# 11_CONSOLE.net
KiCad netlist of a schematic drawn in Altium Designer
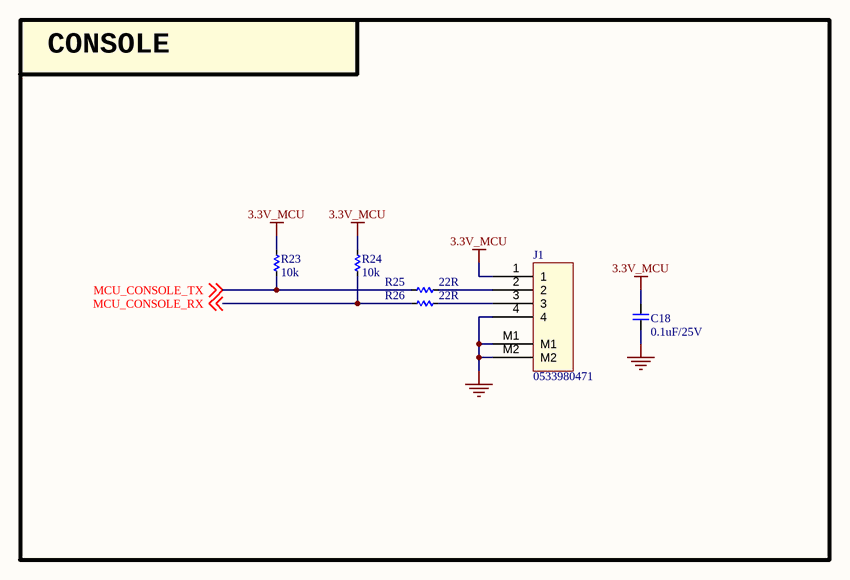
[diagram p0: 11_CONSOLE.SchDoc]

(export (version "E")
  (design (tool "Eeschema 10.0.6"))
  (components
    (comp (ref "C18")
      (value "0.1uF/25V")
      (footprint "CAP_C_1005X60")
      (description "CAP")
      (libsource (lib "LABLIB") (part "_CAP_C_2"))
    )
    (comp (ref "J1")
      (value "0533980471")
      (footprint "MOLEX_0533980471")
      (libsource (lib "LABLIB") (part "Header 4x1_2M"))
    )
    (comp (ref "R23")
      (value "10k")
      (footprint "RES_C_1005X40")
      (description "RES")
      (libsource (lib "LABLIB") (part "_RES_B_2"))
    )
    (comp (ref "R24")
      (value "10k")
      (footprint "RES_C_1005X40")
      (description "RES")
      (libsource (lib "LABLIB") (part "_RES_B_2"))
    )
    (comp (ref "R25")
      (value "22R")
      (footprint "RES_C_1005X40")
      (description "RES")
      (libsource (lib "LABLIB") (part "_RES_B_2"))
    )
    (comp (ref "R26")
      (value "22R")
      (footprint "RES_C_1005X40")
      (description "RES")
      (libsource (lib "LABLIB") (part "_RES_B_2"))
    )
  )
  (nets
    (net (code "1") (name "3.3V_MCU") (class "Default")
      (node (ref "C18") (pin "2") (pinfunction "2_2") (pintype "passive"))
      (node (ref "J1") (pin "1") (pinfunction "1_1") (pintype "passive"))
      (node (ref "R23") (pin "2") (pinfunction "2_2") (pintype "passive"))
      (node (ref "R24") (pin "2") (pinfunction "2_2") (pintype "passive"))
    )
    (net (code "2") (name "GND") (class "Default")
      (node (ref "C18") (pin "1") (pinfunction "1_1") (pintype "passive"))
      (node (ref "J1") (pin "4") (pinfunction "4_4") (pintype "passive"))
      (node (ref "J1") (pin "M1") (pinfunction "M1_M1") (pintype "passive"))
      (node (ref "J1") (pin "M2") (pinfunction "M2_M2") (pintype "passive"))
    )
    (net (code "3") (name "MCU_CONSOLE_RX") (class "Default")
      (node (ref "R24") (pin "1") (pinfunction "1_1") (pintype "passive"))
      (node (ref "R26") (pin "2") (pinfunction "2_2") (pintype "passive"))
    )
    (net (code "4") (name "MCU_CONSOLE_TX") (class "Default")
      (node (ref "R23") (pin "1") (pinfunction "1_1") (pintype "passive"))
      (node (ref "R25") (pin "2") (pinfunction "2_2") (pintype "passive"))
    )
    (net (code "5") (name "Net-(J1-Pad2)") (class "Default")
      (node (ref "J1") (pin "2") (pinfunction "2_2") (pintype "passive"))
      (node (ref "R25") (pin "1") (pinfunction "1_1") (pintype "passive"))
    )
    (net (code "6") (name "Net-(J1-Pad3)") (class "Default")
      (node (ref "J1") (pin "3") (pinfunction "3_3") (pintype "passive"))
      (node (ref "R26") (pin "1") (pinfunction "1_1") (pintype "passive"))
    )
  )
)
